# final.net
KiCad netlist of a schematic drawn in Altium Designer
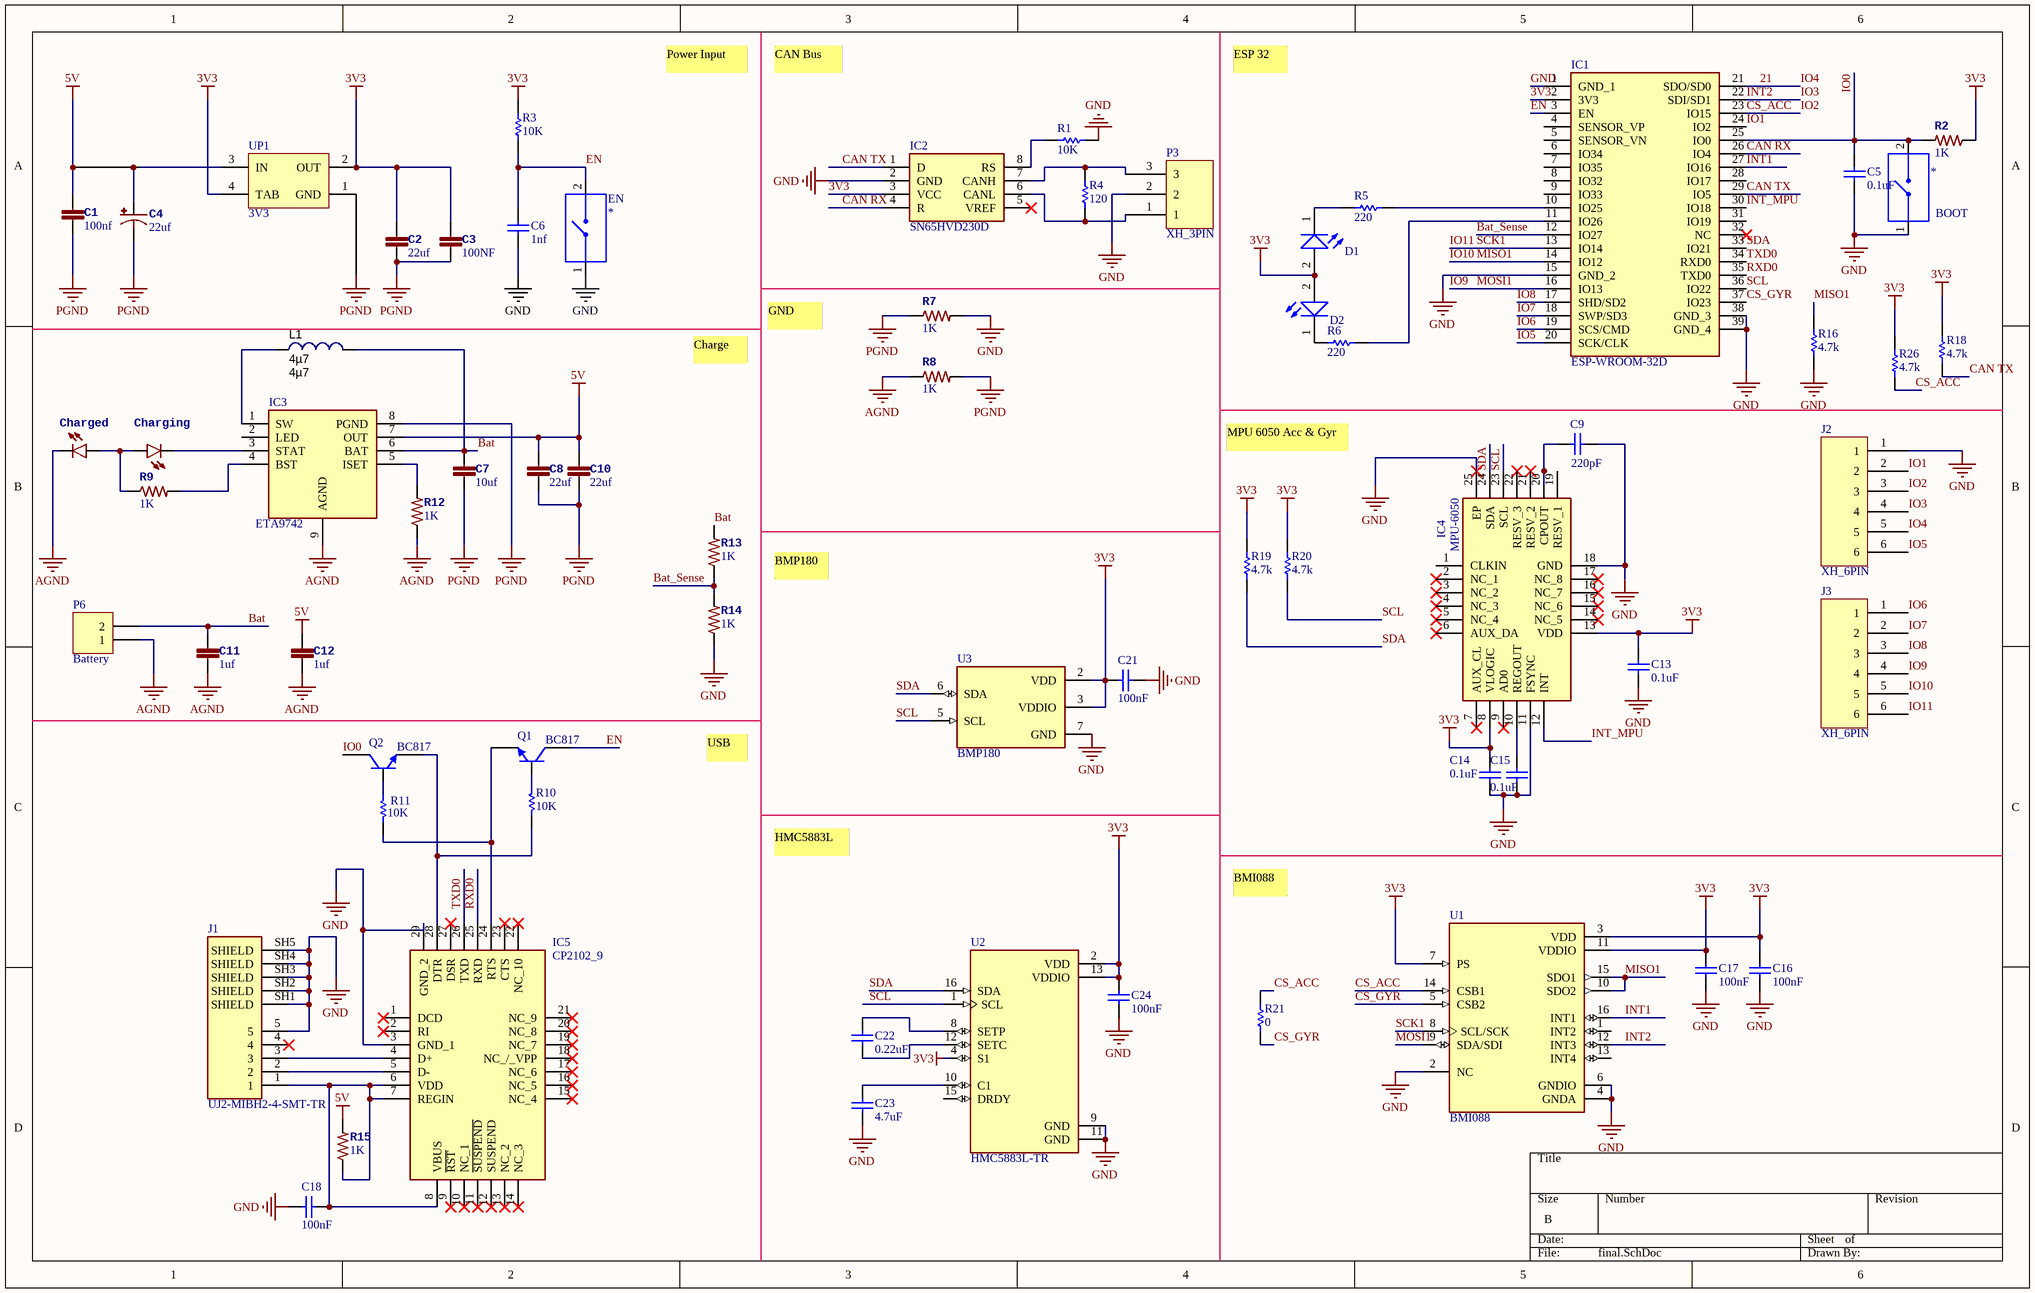
[diagram p0: final.SchDoc]

(export (version "E")
  (design (tool "Eeschema 10.0.6"))
  (components
    (comp (ref "BOOT")
      (value "1437566-4")
      (footprint "SW_1437566-4")
      (description "Switch Tactile OFF _ON_ SPST Rectangular Button Gull Wing 0.05A 12VDC 1.77N SMD T/R")
      (fields
        (field (name "MF") "TE Connectivity")
        (field (name "DIGI-KEY_PART_NUMBER") "450-1758-1-ND")
        (field (name "COMMENT_1") "*")
      )
      (libsource (lib "1437566-4") (part "1437566-4"))
    )
    (comp (ref "C1")
      (value "100nf")
      (footprint "_0805")
      (fields (field (name "Comment") "Cap"))
      (libsource (lib "Passives_Integrated_Library") (part "Cap_1"))
    )
    (comp (ref "C2")
      (value "22uf")
      (footprint "_0805")
      (fields (field (name "Comment") "Cap"))
      (libsource (lib "Passives_Integrated_Library") (part "Cap_1"))
    )
    (comp (ref "C3")
      (value "100NF")
      (footprint "_0805")
      (fields (field (name "Comment") "Cap"))
      (libsource (lib "Passives_Integrated_Library") (part "Cap_1"))
    )
    (comp (ref "C4")
      (value "22uf")
      (footprint "_EIA3216")
      (fields (field (name "Comment") "Cap-Pol"))
      (libsource (lib "Passives_Integrated_Library") (part "Cap-Pol"))
    )
    (comp (ref "C5")
      (value "0.1uF")
      (footprint "C0603")
      (description "CAP 0805")
      (fields (field (name "DESIGNER") "Abbas Basereh"))
      (libsource (lib "Altium") (part "CAP SMD 0805"))
    )
    (comp (ref "C6")
      (value "1nf")
      (footprint "C0603")
      (description "CAP 0805")
      (fields (field (name "DESIGNER") "Abbas Basereh"))
      (libsource (lib "Altium") (part "CAP SMD 0805"))
    )
    (comp (ref "C7")
      (value "10uf")
      (footprint "_0805")
      (fields (field (name "Comment") "Cap"))
      (libsource (lib "Passives_Integrated_Library") (part "Cap_1"))
    )
    (comp (ref "C8")
      (value "22uf")
      (footprint "_0805")
      (fields (field (name "Comment") "Cap"))
      (libsource (lib "Passives_Integrated_Library") (part "Cap_1"))
    )
    (comp (ref "C9")
      (value "220pF")
      (footprint "C0603")
      (description "CAP 0805")
      (fields (field (name "DESIGNER") "Abbas Basereh"))
      (libsource (lib "Altium") (part "CAP SMD 0805"))
    )
    (comp (ref "C10")
      (value "22uf")
      (footprint "_0805")
      (fields (field (name "Comment") "Cap"))
      (libsource (lib "Passives_Integrated_Library") (part "Cap_1"))
    )
    (comp (ref "C11")
      (value "1uf")
      (footprint "_0805")
      (fields (field (name "Comment") "Cap"))
      (libsource (lib "Passives_Integrated_Library") (part "Cap_1"))
    )
    (comp (ref "C12")
      (value "1uf")
      (footprint "_0805")
      (fields (field (name "Comment") "Cap"))
      (libsource (lib "Passives_Integrated_Library") (part "Cap_1"))
    )
    (comp (ref "C13")
      (value "0.1uF")
      (footprint "C0603")
      (description "CAP 0805")
      (fields (field (name "DESIGNER") "Abbas Basereh"))
      (libsource (lib "Altium") (part "CAP SMD 0805"))
    )
    (comp (ref "C14")
      (value "0.1uF")
      (footprint "C0603")
      (description "CAP 0805")
      (fields (field (name "DESIGNER") "Abbas Basereh"))
      (libsource (lib "Altium") (part "CAP SMD 0805"))
    )
    (comp (ref "C15")
      (value "0.1uF")
      (footprint "C0603")
      (description "CAP 0805")
      (fields (field (name "DESIGNER") "Abbas Basereh"))
      (libsource (lib "Altium") (part "CAP SMD 0805"))
    )
    (comp (ref "C16")
      (value "100nF")
      (footprint "C0603")
      (description "CAP 0805")
      (fields (field (name "DESIGNER") "Abbas Basereh"))
      (libsource (lib "Altium") (part "CAP SMD 0805"))
    )
    (comp (ref "C17")
      (value "100nF")
      (footprint "C0603")
      (description "CAP 0805")
      (fields (field (name "DESIGNER") "Abbas Basereh"))
      (libsource (lib "Altium") (part "CAP SMD 0805"))
    )
    (comp (ref "C18")
      (value "100nF")
      (footprint "C0603")
      (description "CAP 0805")
      (fields (field (name "DESIGNER") "Abbas Basereh"))
      (libsource (lib "Altium") (part "CAP SMD 0805"))
    )
    (comp (ref "C21")
      (value "100nF")
      (footprint "C0603")
      (description "CAP 0805")
      (fields (field (name "DESIGNER") "Abbas Basereh"))
      (libsource (lib "Altium") (part "CAP SMD 0805"))
    )
    (comp (ref "C22")
      (value "0.22uF")
      (footprint "C0603")
      (description "CAP 0805")
      (fields (field (name "DESIGNER") "Abbas Basereh"))
      (libsource (lib "Altium") (part "CAP SMD 0805"))
    )
    (comp (ref "C23")
      (value "4.7uF")
      (footprint "C0603")
      (description "CAP 0805")
      (fields (field (name "DESIGNER") "Abbas Basereh"))
      (libsource (lib "Altium") (part "CAP SMD 0805"))
    )
    (comp (ref "C24")
      (value "100nF")
      (footprint "C0603")
      (description "CAP 0805")
      (fields (field (name "DESIGNER") "Abbas Basereh"))
      (libsource (lib "Altium") (part "CAP SMD 0805"))
    )
    (comp (ref "Charged")
      (value "LED")
      (footprint "_LED-0805")
      (libsource (lib "Diodes_Integrated_Library") (part "LED"))
    )
    (comp (ref "Charging")
      (value "LED")
      (footprint "_LED-0805")
      (libsource (lib "Diodes_Integrated_Library") (part "LED"))
    )
    (comp (ref "D1")
      (value "LED SMD PACKAGE")
      (footprint "LED_SMD_0805")
      (description "SMD Mono-color Chip LED Waterclear")
      (fields (field (name "PART NUMBER") "150080BS75000") (field (name "PUBLISHER") "Ali Hafizi"))
      (libsource (lib "Altium") (part "LED SMD PACKAGE"))
    )
    (comp (ref "D2")
      (value "LED SMD PACKAGE")
      (footprint "LED_SMD_0805")
      (description "SMD Mono-color Chip LED Waterclear")
      (fields (field (name "PART NUMBER") "150080BS75000") (field (name "PUBLISHER") "Ali Hafizi"))
      (libsource (lib "Altium") (part "LED SMD PACKAGE"))
    )
    (comp (ref "EN")
      (value "1437566-4")
      (footprint "SW_1437566-4")
      (description "Switch Tactile OFF _ON_ SPST Rectangular Button Gull Wing 0.05A 12VDC 1.77N SMD T/R")
      (fields
        (field (name "MF") "TE Connectivity")
        (field (name "DIGI-KEY_PART_NUMBER") "450-1758-1-ND")
        (field (name "COMMENT_1") "*")
      )
      (libsource (lib "1437566-4") (part "1437566-4"))
    )
    (comp (ref "IC1")
      (value "ESP-WROOM-32D")
      (footprint "SamacSys:ESPWROOM32D")
      (description "Integrated Circuit")
      (fields (field (name "MOUSER PART NUMBER") "356-ESP-WROOM-32D"))
      (libsource (lib "SamacSys") (part "ESP-WROOM-32D"))
    )
    (comp (ref "IC2")
      (value "SN65HVD230D")
      (footprint "SamacSys:SOIC127P600X175-8N")
      (description "Integrated Circuit")
      (fields (field (name "MOUSER PART NUMBER") "595-SN65HVD230D"))
      (libsource (lib "*") (part "SN65HVD230D"))
    )
    (comp (ref "IC3")
      (value "ETA9742")
      (footprint "SamacSys:SOIC127P600X175-9N")
      (description "Integrated Circuit")
      (libsource (lib "*") (part "ETA9742"))
    )
    (comp (ref "IC4")
      (value "MPU-6050")
      (footprint "SamacSys:QFN50P400X400X95-25N")
      (description "Integrated Circuit")
      (fields (field (name "MOUSER PART NUMBER") "410-MPU-6050"))
      (libsource (lib "*") (part "MPU-6050"))
    )
    (comp (ref "IC5")
      (value "CP2102_9")
      (footprint "SamacSys:QFN50P500X500X105-29N-D")
      (description "Integrated Circuit")
      (fields (field (name "MANUFACTURER_PART_NUMBER") "CP2102/9"))
      (libsource (lib "*") (part "CP2102_9"))
    )
    (comp (ref "J1")
      (value "UJ2-MIBH2-4-SMT-TR")
      (footprint "CUI_UJ2-MIBH2-4-SMT-TR")
      (description "Micro B, USB 2.0, 1.8 A, Right Angle, Surface Mount _SMT_, USB Receptacle")
      (fields (field (name "MF") "CUI Devices"))
      (libsource (lib "UJ2-MIBH2-4-SMT-TR") (part "UJ2-MIBH2-4-SMT-TR"))
    )
    (comp (ref "J2")
      (value "XH_6PIN")
      (footprint "XH_6PIN")
      (libsource (lib "Others_Integrated_Library") (part "XH_6PIN"))
    )
    (comp (ref "J3")
      (value "XH_6PIN")
      (footprint "XH_6PIN")
      (libsource (lib "Others_Integrated_Library") (part "XH_6PIN"))
    )
    (comp (ref "L1")
      (value "4µ7")
      (footprint "Inductor SMD 3x3.2mm")
      (description "Inductor 4.7µH SMD 3x3.2mm")
      (fields (field (name "TOLERANCE") "±20%") (field (name "ALTIUM_VALUE") "4µ7"))
      (libsource (lib "Altium") (part "Inductor 4.7µH SMD 3x3.2mm"))
    )
    (comp (ref "P3")
      (value "XH_3PIN")
      (footprint "XH_3PIN")
      (libsource (lib "Others_Integrated_Library") (part "XH_3PIN"))
    )
    (comp (ref "P6")
      (value "Battery")
      (footprint "HDR1X2")
      (description "Header, 2-Pin")
      (fields (field (name "PUBLISHER") "Altium Limited"))
      (libsource (lib "Altium") (part "Header 2"))
    )
    (comp (ref "Q1")
      (value "BC817")
      (footprint "SOT23_N")
      (description "45 V, 500 mA NPN general-purpose transistors")
      (fields (field (name "PUBLISHER") "Abbas Basereh"))
      (libsource (lib "Altium") (part "BC817"))
    )
    (comp (ref "Q2")
      (value "BC817")
      (footprint "SOT23_N")
      (description "45 V, 500 mA NPN general-purpose transistors")
      (fields (field (name "PUBLISHER") "Abbas Basereh"))
      (libsource (lib "Altium") (part "BC817"))
    )
    (comp (ref "R1")
      (value "10K")
      (footprint "SMD-0603-RES")
      (description "Resistor SMD 0603")
      (libsource (lib "Resistor") (part "Resistor SMD 0603"))
    )
    (comp (ref "R2")
      (value "1K")
      (footprint "_0805")
      (fields (field (name "Comment") "Resistor"))
      (libsource (lib "Passives_Integrated_Library") (part "Resistor"))
    )
    (comp (ref "R3")
      (value "10K")
      (footprint "RES0805")
      (description "TOTAL SMD RESISTOR PACK")
      (fields (field (name "DESIGNER") "Abbas Basereh"))
      (libsource (lib "Altium") (part "RES SMD PACKAGE"))
    )
    (comp (ref "R4")
      (value "120")
      (footprint "SMD-0603-RES")
      (description "Resistor SMD 0603")
      (libsource (lib "Resistor") (part "Resistor SMD 0603"))
    )
    (comp (ref "R5")
      (value "220")
      (footprint "SMD-0603-RES")
      (description "Resistor SMD 0603")
      (libsource (lib "Resistor") (part "Resistor SMD 0603"))
    )
    (comp (ref "R6")
      (value "220")
      (footprint "SMD-0603-RES")
      (description "Resistor SMD 0603")
      (libsource (lib "Resistor") (part "Resistor SMD 0603"))
    )
    (comp (ref "R7")
      (value "1K")
      (footprint "_0805")
      (fields (field (name "Comment") "Resistor"))
      (libsource (lib "Passives_Integrated_Library") (part "Resistor"))
    )
    (comp (ref "R8")
      (value "1K")
      (footprint "_0805")
      (fields (field (name "Comment") "Resistor"))
      (libsource (lib "Passives_Integrated_Library") (part "Resistor"))
    )
    (comp (ref "R9")
      (value "1K")
      (footprint "_0805")
      (fields (field (name "Comment") "Resistor"))
      (libsource (lib "Passives_Integrated_Library") (part "Resistor"))
    )
    (comp (ref "R10")
      (value "10K")
      (footprint "SMD-0603-RES")
      (description "Resistor SMD 0603")
      (libsource (lib "Resistor") (part "Resistor SMD 0603"))
    )
    (comp (ref "R11")
      (value "10K")
      (footprint "SMD-0603-RES")
      (description "Resistor SMD 0603")
      (libsource (lib "Resistor") (part "Resistor SMD 0603"))
    )
    (comp (ref "R12")
      (value "1K")
      (footprint "_0805")
      (fields (field (name "Comment") "Resistor"))
      (libsource (lib "Passives_Integrated_Library") (part "Resistor"))
    )
    (comp (ref "R13")
      (value "1K")
      (footprint "_0805")
      (fields (field (name "Comment") "Resistor"))
      (libsource (lib "Passives_Integrated_Library") (part "Resistor"))
    )
    (comp (ref "R14")
      (value "1K")
      (footprint "_0805")
      (fields (field (name "Comment") "Resistor"))
      (libsource (lib "Passives_Integrated_Library") (part "Resistor"))
    )
    (comp (ref "R15")
      (value "1K")
      (footprint "_0805")
      (fields (field (name "Comment") "Resistor"))
      (libsource (lib "Passives_Integrated_Library") (part "Resistor"))
    )
    (comp (ref "R16")
      (value "4.7k")
      (footprint "SMD-0603-RES")
      (description "Resistor SMD 0603")
      (libsource (lib "Resistor") (part "Resistor SMD 0603"))
    )
    (comp (ref "R18")
      (value "4.7k")
      (footprint "SMD-0603-RES")
      (description "Resistor SMD 0603")
      (libsource (lib "Resistor") (part "Resistor SMD 0603"))
    )
    (comp (ref "R19")
      (value "4.7k")
      (footprint "SMD-0603-RES")
      (description "Resistor SMD 0603")
      (libsource (lib "Resistor") (part "Resistor SMD 0603"))
    )
    (comp (ref "R20")
      (value "4.7k")
      (footprint "SMD-0603-RES")
      (description "Resistor SMD 0603")
      (libsource (lib "Resistor") (part "Resistor SMD 0603"))
    )
    (comp (ref "R21")
      (value "0")
      (footprint "SMD-0603-RES")
      (description "Resistor SMD 0603")
      (libsource (lib "Resistor") (part "Resistor SMD 0603"))
    )
    (comp (ref "R26")
      (value "4.7k")
      (footprint "SMD-0603-RES")
      (description "Resistor SMD 0603")
      (libsource (lib "Resistor") (part "Resistor SMD 0603"))
    )
    (comp (ref "U1")
      (value "BMI088")
      (footprint "PQFN50P450X300X100-16N")
      (description "Accelerometer, Gyroscope, 6 Axis Sensor IÂ²C, SPI Output")
      (fields (field (name "MF") "Bosch Sensortec"))
      (libsource (lib "BMI088") (part "BMI088"))
    )
    (comp (ref "U2")
      (value "HMC5883L-TR")
      (footprint "XDCR_HMC5883L-TR")
      (description "Magnetoresistive Sensor X, Y, Z Axis 16-LCC")
      (fields (field (name "MF") "Honeywell") (field (name "MP") "HMC5883LTR"))
      (libsource (lib "HMC5883L-TR") (part "HMC5883L-TR"))
    )
    (comp (ref "U3")
      (value "BMP180")
      (footprint "BMP180")
      (description "Pressure Sensor 4.35PSI ~ 15.95PSI _30kPa ~ 110kPa_ Absolute 16 ~ 19 b 7-VLGA")
      (fields (field (name "MF") "Bosch Sensortec") (field (name "DIGI-KEY_PART_NUMBER") "828-1027-1-ND"))
      (libsource (lib "BMP180") (part "BMP180"))
    )
    (comp (ref "UP1")
      (value "3V3")
      (footprint "SOT223_N")
      (description "x.x Volt, 800mA Low-Dropout Linear Regulator, 4-pin SOT-223")
      (fields (field (name "DESIGNER") "Ali Hafizi"))
      (libsource (lib "Altium") (part "AMS1117-x.x"))
    )
  )
  (nets
    (net (code "1") (name "/21") (class "Default")
      (node (ref "IC1") (pin "21") (pinfunction "SDO/SD0_21") (pintype "passive"))
      (node (ref "J2") (pin "5") (pinfunction "5_5") (pintype "passive"))
    )
    (net (code "2") (name "/Bat") (class "Default")
      (node (ref "C11") (pin "1") (pinfunction "1_1") (pintype "passive"))
      (node (ref "C7") (pin "1") (pinfunction "1_1") (pintype "passive"))
      (node (ref "IC3") (pin "6") (pinfunction "BAT_6") (pintype "passive"))
      (node (ref "L1") (pin "2") (pinfunction "2_2") (pintype "passive"))
      (node (ref "P6") (pin "2") (pinfunction "2_2") (pintype "passive"))
      (node (ref "R13") (pin "2") (pinfunction "2_2") (pintype "passive"))
    )
    (net (code "3") (name "/Bat_Sense") (class "Default")
      (node (ref "IC1") (pin "12") (pinfunction "IO27_12") (pintype "passive"))
      (node (ref "R13") (pin "1") (pinfunction "1_1") (pintype "passive"))
      (node (ref "R14") (pin "2") (pinfunction "2_2") (pintype "passive"))
    )
    (net (code "4") (name "/CAN RX") (class "Default")
      (node (ref "IC1") (pin "26") (pinfunction "IO4_26") (pintype "passive"))
      (node (ref "IC2") (pin "4") (pinfunction "R_4") (pintype "passive"))
    )
    (net (code "5") (name "/CAN TX") (class "Default")
      (node (ref "IC1") (pin "29") (pinfunction "IO5_29") (pintype "passive"))
      (node (ref "IC2") (pin "1") (pinfunction "D_1") (pintype "passive"))
      (node (ref "R18") (pin "1") (pinfunction "1_1") (pintype "passive"))
    )
    (net (code "6") (name "/CS_ACC") (class "Default")
      (node (ref "IC1") (pin "23") (pinfunction "IO15_23") (pintype "passive"))
      (node (ref "J2") (pin "3") (pinfunction "3_3") (pintype "passive"))
      (node (ref "R21") (pin "2") (pinfunction "2_2") (pintype "passive"))
      (node (ref "R26") (pin "1") (pinfunction "1_1") (pintype "passive"))
      (node (ref "U1") (pin "14") (pinfunction "CSB1_14") (pintype "input"))
    )
    (net (code "7") (name "/CS_GYR") (class "Default")
      (node (ref "IC1") (pin "37") (pinfunction "IO23_37") (pintype "passive"))
      (node (ref "R21") (pin "1") (pinfunction "1_1") (pintype "passive"))
      (node (ref "U1") (pin "5") (pinfunction "CSB2_5") (pintype "input"))
    )
    (net (code "8") (name "/EN") (class "Default")
      (node (ref "C6") (pin "2") (pinfunction "2_2") (pintype "passive"))
      (node (ref "EN") (pin "2") (pinfunction "2_2") (pintype "passive"))
      (node (ref "IC1") (pin "3") (pinfunction "EN_3") (pintype "passive"))
      (node (ref "Q1") (pin "3") (pinfunction "C_3") (pintype "passive"))
      (node (ref "R3") (pin "1") (pinfunction "1_1") (pintype "passive"))
    )
    (net (code "9") (name "/INT1") (class "Default")
      (node (ref "IC1") (pin "27") (pinfunction "IO16_27") (pintype "passive"))
      (node (ref "U1") (pin "16") (pinfunction "INT1_16") (pintype "bidirectional"))
    )
    (net (code "10") (name "/INT2") (class "Default")
      (node (ref "IC1") (pin "22") (pinfunction "SDI/SD1_22") (pintype "passive"))
      (node (ref "J2") (pin "4") (pinfunction "4_4") (pintype "passive"))
      (node (ref "U1") (pin "12") (pinfunction "INT3_12") (pintype "bidirectional"))
    )
    (net (code "11") (name "/INT_MPU") (class "Default")
      (node (ref "IC1") (pin "30") (pinfunction "IO18_30") (pintype "passive"))
      (node (ref "IC4") (pin "12") (pinfunction "INT_12") (pintype "passive"))
    )
    (net (code "12") (name "/IO0") (class "Default")
      (node (ref "BOOT") (pin "2") (pinfunction "2_2") (pintype "passive"))
      (node (ref "C5") (pin "2") (pinfunction "2_2") (pintype "passive"))
      (node (ref "IC1") (pin "25") (pinfunction "IO0_25") (pintype "passive"))
      (node (ref "Q2") (pin "3") (pinfunction "C_3") (pintype "passive"))
      (node (ref "R2") (pin "2") (pinfunction "2_2") (pintype "passive"))
    )
    (net (code "13") (name "/IO1") (class "Default")
      (node (ref "IC1") (pin "24") (pinfunction "IO2_24") (pintype "passive"))
      (node (ref "J2") (pin "2") (pinfunction "2_2") (pintype "passive"))
    )
    (net (code "14") (name "/IO5") (class "Default")
      (node (ref "IC1") (pin "20") (pinfunction "SCK/CLK_20") (pintype "passive"))
      (node (ref "J2") (pin "6") (pinfunction "6_6") (pintype "passive"))
    )
    (net (code "15") (name "/IO6") (class "Default")
      (node (ref "IC1") (pin "19") (pinfunction "SCS/CMD_19") (pintype "passive"))
      (node (ref "J3") (pin "1") (pinfunction "1_1") (pintype "passive"))
    )
    (net (code "16") (name "/IO7") (class "Default")
      (node (ref "IC1") (pin "18") (pinfunction "SWP/SD3_18") (pintype "passive"))
      (node (ref "J3") (pin "2") (pinfunction "2_2") (pintype "passive"))
    )
    (net (code "17") (name "/IO8") (class "Default")
      (node (ref "IC1") (pin "17") (pinfunction "SHD/SD2_17") (pintype "passive"))
      (node (ref "J3") (pin "3") (pinfunction "3_3") (pintype "passive"))
    )
    (net (code "18") (name "/IO9") (class "Default")
      (node (ref "IC1") (pin "16") (pinfunction "IO13_16") (pintype "passive"))
      (node (ref "J3") (pin "4") (pinfunction "4_4") (pintype "passive"))
      (node (ref "U1") (pin "9") (pinfunction "SDA/SDI_9") (pintype "bidirectional"))
    )
    (net (code "19") (name "/IO10") (class "Default")
      (node (ref "IC1") (pin "14") (pinfunction "IO12_14") (pintype "passive"))
      (node (ref "J3") (pin "5") (pinfunction "5_5") (pintype "passive"))
      (node (ref "R16") (pin "2") (pinfunction "2_2") (pintype "passive"))
      (node (ref "U1") (pin "10") (pinfunction "SDO2_10") (pintype "output"))
      (node (ref "U1") (pin "15") (pinfunction "SDO1_15") (pintype "output"))
    )
    (net (code "20") (name "/IO11") (class "Default")
      (node (ref "IC1") (pin "13") (pinfunction "IO14_13") (pintype "passive"))
      (node (ref "J3") (pin "6") (pinfunction "6_6") (pintype "passive"))
      (node (ref "U1") (pin "8") (pinfunction "SCL/SCK_8") (pintype "input"))
    )
    (net (code "21") (name "/RXD0") (class "Default")
      (node (ref "IC1") (pin "35") (pinfunction "TXD0_35") (pintype "passive"))
      (node (ref "IC5") (pin "25") (pinfunction "RXD_25") (pintype "passive"))
    )
    (net (code "22") (name "/SCL") (class "Default")
      (node (ref "IC1") (pin "36") (pinfunction "IO22_36") (pintype "passive"))
      (node (ref "IC4") (pin "23") (pinfunction "SCL_23") (pintype "passive"))
      (node (ref "R20") (pin "1") (pinfunction "1_1") (pintype "passive"))
      (node (ref "U2") (pin "1") (pinfunction "SCL_1") (pintype "input"))
      (node (ref "U3") (pin "5") (pinfunction "SCL_5") (pintype "input"))
    )
    (net (code "23") (name "/SDA") (class "Default")
      (node (ref "IC1") (pin "33") (pinfunction "IO21_33") (pintype "passive"))
      (node (ref "IC4") (pin "24") (pinfunction "SDA_24") (pintype "passive"))
      (node (ref "R19") (pin "1") (pinfunction "1_1") (pintype "passive"))
      (node (ref "U2") (pin "16") (pinfunction "SDA_16") (pintype "input"))
      (node (ref "U3") (pin "6") (pinfunction "SDA_6") (pintype "bidirectional"))
    )
    (net (code "24") (name "/TXD0") (class "Default")
      (node (ref "IC1") (pin "34") (pinfunction "RXD0_34") (pintype "passive"))
      (node (ref "IC5") (pin "26") (pinfunction "TXD_26") (pintype "passive"))
    )
    (net (code "25") (name "3V3") (class "Default")
      (node (ref "C13") (pin "2") (pinfunction "2_2") (pintype "passive"))
      (node (ref "C14") (pin "1") (pinfunction "1_1") (pintype "passive"))
      (node (ref "C16") (pin "2") (pinfunction "2_2") (pintype "passive"))
      (node (ref "C17") (pin "2") (pinfunction "2_2") (pintype "passive"))
      (node (ref "C2") (pin "1") (pinfunction "1_1") (pintype "passive"))
      (node (ref "C21") (pin "2") (pinfunction "2_2") (pintype "passive"))
      (node (ref "C24") (pin "1") (pinfunction "1_1") (pintype "passive"))
      (node (ref "C3") (pin "1") (pinfunction "1_1") (pintype "passive"))
      (node (ref "D1") (pin "2") (pinfunction "A_2") (pintype "passive"))
      (node (ref "D2") (pin "2") (pinfunction "A_2") (pintype "passive"))
      (node (ref "IC1") (pin "2") (pinfunction "3V3_2") (pintype "passive"))
      (node (ref "IC2") (pin "3") (pinfunction "VCC_3") (pintype "passive"))
      (node (ref "IC4") (pin "13") (pinfunction "VDD_13") (pintype "passive"))
      (node (ref "IC4") (pin "8") (pinfunction "VLOGIC_8") (pintype "passive"))
      (node (ref "R18") (pin "2") (pinfunction "2_2") (pintype "passive"))
      (node (ref "R19") (pin "2") (pinfunction "2_2") (pintype "passive"))
      (node (ref "R2") (pin "1") (pinfunction "1_1") (pintype "passive"))
      (node (ref "R20") (pin "2") (pinfunction "2_2") (pintype "passive"))
      (node (ref "R26") (pin "2") (pinfunction "2_2") (pintype "passive"))
      (node (ref "R3") (pin "2") (pinfunction "2_2") (pintype "passive"))
      (node (ref "U1") (pin "11") (pinfunction "VDDIO_11") (pintype "power_in"))
      (node (ref "U1") (pin "3") (pinfunction "VDD_3") (pintype "power_in"))
      (node (ref "U1") (pin "7") (pinfunction "PS_7") (pintype "input"))
      (node (ref "U2") (pin "13") (pinfunction "VDDIO_13") (pintype "power_in"))
      (node (ref "U2") (pin "2") (pinfunction "VDD_2") (pintype "power_in"))
      (node (ref "U2") (pin "4") (pinfunction "S1_4") (pintype "bidirectional"))
      (node (ref "U3") (pin "2") (pinfunction "VDD_2") (pintype "power_in"))
      (node (ref "U3") (pin "3") (pinfunction "VDDIO_3") (pintype "power_in"))
      (node (ref "UP1") (pin "2") (pinfunction "OUT_2") (pintype "power_in"))
      (node (ref "UP1") (pin "4") (pinfunction "TAB_4") (pintype "power_in"))
    )
    (net (code "26") (name "5V") (class "Default")
      (node (ref "C1") (pin "1") (pinfunction "1_1") (pintype "passive"))
      (node (ref "C10") (pin "1") (pinfunction "1_1") (pintype "passive"))
      (node (ref "C12") (pin "1") (pinfunction "1_1") (pintype "passive"))
      (node (ref "C4") (pin "+") (pinfunction "+_+") (pintype "passive"))
      (node (ref "C8") (pin "1") (pinfunction "1_1") (pintype "passive"))
      (node (ref "IC3") (pin "7") (pinfunction "OUT_7") (pintype "passive"))
      (node (ref "R15") (pin "2") (pinfunction "2_2") (pintype "passive"))
      (node (ref "UP1") (pin "3") (pinfunction "IN_3") (pintype "power_in"))
    )
    (net (code "27") (name "AGND") (class "Default")
      (node (ref "C11") (pin "2") (pinfunction "2_2") (pintype "passive"))
      (node (ref "C12") (pin "2") (pinfunction "2_2") (pintype "passive"))
      (node (ref "Charged") (pin "K") (pinfunction "K_K") (pintype "passive"))
      (node (ref "IC3") (pin "9") (pinfunction "AGND_9") (pintype "passive"))
      (node (ref "P6") (pin "1") (pinfunction "1_1") (pintype "passive"))
      (node (ref "R12") (pin "1") (pinfunction "1_1") (pintype "passive"))
      (node (ref "R8") (pin "1") (pinfunction "1_1") (pintype "passive"))
    )
    (net (code "28") (name "GND") (class "Default")
      (node (ref "BOOT") (pin "1") (pinfunction "1_1") (pintype "passive"))
      (node (ref "C13") (pin "1") (pinfunction "1_1") (pintype "passive"))
      (node (ref "C14") (pin "2") (pinfunction "2_2") (pintype "passive"))
      (node (ref "C15") (pin "1") (pinfunction "1_1") (pintype "passive"))
      (node (ref "C16") (pin "1") (pinfunction "1_1") (pintype "passive"))
      (node (ref "C17") (pin "1") (pinfunction "1_1") (pintype "passive"))
      (node (ref "C18") (pin "2") (pinfunction "2_2") (pintype "passive"))
      (node (ref "C21") (pin "1") (pinfunction "1_1") (pintype "passive"))
      (node (ref "C23") (pin "1") (pinfunction "1_1") (pintype "passive"))
      (node (ref "C24") (pin "2") (pinfunction "2_2") (pintype "passive"))
      (node (ref "C5") (pin "1") (pinfunction "1_1") (pintype "passive"))
      (node (ref "C6") (pin "1") (pinfunction "1_1") (pintype "passive"))
      (node (ref "C9") (pin "1") (pinfunction "1_1") (pintype "passive"))
      (node (ref "EN") (pin "1") (pinfunction "1_1") (pintype "passive"))
      (node (ref "IC1") (pin "1") (pinfunction "GND_1_1") (pintype "passive"))
      (node (ref "IC1") (pin "15") (pinfunction "GND_2_15") (pintype "passive"))
      (node (ref "IC1") (pin "38") (pinfunction "GND_3_38") (pintype "passive"))
      (node (ref "IC1") (pin "39") (pinfunction "GND_4_39") (pintype "passive"))
      (node (ref "IC2") (pin "2") (pinfunction "GND_2") (pintype "passive"))
      (node (ref "IC4") (pin "11") (pinfunction "FSYNC_11") (pintype "passive"))
      (node (ref "IC4") (pin "18") (pinfunction "GND_18") (pintype "passive"))
      (node (ref "IC4") (pin "25") (pinfunction "EP_25") (pintype "passive"))
      (node (ref "IC5") (pin "29") (pinfunction "GND_2_29") (pintype "passive"))
      (node (ref "IC5") (pin "3") (pinfunction "GND_1_3") (pintype "passive"))
      (node (ref "J1") (pin "5") (pinfunction "5_5") (pintype "passive"))
      (node (ref "J1") (pin "SH1") (pinfunction "SHIELD_SH1") (pintype "passive"))
      (node (ref "J1") (pin "SH2") (pinfunction "SHIELD_SH2") (pintype "passive"))
      (node (ref "J1") (pin "SH3") (pinfunction "SHIELD_SH3") (pintype "passive"))
      (node (ref "J1") (pin "SH4") (pinfunction "SHIELD_SH4") (pintype "passive"))
      (node (ref "J1") (pin "SH5") (pinfunction "SHIELD_SH5") (pintype "passive"))
      (node (ref "J2") (pin "1") (pinfunction "1_1") (pintype "passive"))
      (node (ref "P3") (pin "2") (pinfunction "2_2") (pintype "passive"))
      (node (ref "R1") (pin "1") (pinfunction "1_1") (pintype "passive"))
      (node (ref "R14") (pin "1") (pinfunction "1_1") (pintype "passive"))
      (node (ref "R16") (pin "1") (pinfunction "1_1") (pintype "passive"))
      (node (ref "R7") (pin "2") (pinfunction "2_2") (pintype "passive"))
      (node (ref "U1") (pin "2") (pinfunction "NC_2") (pintype "passive"))
      (node (ref "U1") (pin "4") (pinfunction "GNDA_4") (pintype "power_in"))
      (node (ref "U1") (pin "6") (pinfunction "GNDIO_6") (pintype "power_in"))
      (node (ref "U2") (pin "11") (pinfunction "GND_11") (pintype "power_in"))
      (node (ref "U2") (pin "9") (pinfunction "GND_9") (pintype "power_in"))
      (node (ref "U3") (pin "7") (pinfunction "GND_7") (pintype "power_in"))
    )
    (net (code "29") (name "Net-(Charged-PadA)") (class "Default")
      (node (ref "Charged") (pin "A") (pinfunction "A_A") (pintype "passive"))
      (node (ref "Charging") (pin "A") (pinfunction "A_A") (pintype "passive"))
      (node (ref "R9") (pin "1") (pinfunction "1_1") (pintype "passive"))
    )
    (net (code "30") (name "Net-(D1-K)") (class "Default")
      (node (ref "D1") (pin "1") (pinfunction "K_1") (pintype "passive"))
      (node (ref "R5") (pin "2") (pinfunction "2_2") (pintype "passive"))
    )
    (net (code "31") (name "Net-(D2-K)") (class "Default")
      (node (ref "D2") (pin "1") (pinfunction "K_1") (pintype "passive"))
      (node (ref "R6") (pin "2") (pinfunction "2_2") (pintype "passive"))
    )
    (net (code "32") (name "Net-(IC1-IO25)") (class "Default")
      (node (ref "IC1") (pin "10") (pinfunction "IO25_10") (pintype "passive"))
      (node (ref "R5") (pin "1") (pinfunction "1_1") (pintype "passive"))
    )
    (net (code "33") (name "Net-(IC1-IO26)") (class "Default")
      (node (ref "IC1") (pin "11") (pinfunction "IO26_11") (pintype "passive"))
      (node (ref "R6") (pin "1") (pinfunction "1_1") (pintype "passive"))
    )
    (net (code "34") (name "Net-(IC2-CANH)") (class "Default")
      (node (ref "IC2") (pin "7") (pinfunction "CANH_7") (pintype "passive"))
      (node (ref "P3") (pin "3") (pinfunction "3_3") (pintype "passive"))
      (node (ref "R4") (pin "2") (pinfunction "2_2") (pintype "passive"))
    )
    (net (code "35") (name "Net-(IC2-CANL)") (class "Default")
      (node (ref "IC2") (pin "6") (pinfunction "CANL_6") (pintype "passive"))
      (node (ref "P3") (pin "1") (pinfunction "1_1") (pintype "passive"))
      (node (ref "R4") (pin "1") (pinfunction "1_1") (pintype "passive"))
    )
    (net (code "36") (name "Net-(IC2-RS)") (class "Default")
      (node (ref "IC2") (pin "8") (pinfunction "RS_8") (pintype "passive"))
      (node (ref "R1") (pin "2") (pinfunction "2_2") (pintype "passive"))
    )
    (net (code "37") (name "Net-(IC3-BST)") (class "Default")
      (node (ref "IC3") (pin "4") (pinfunction "BST_4") (pintype "passive"))
      (node (ref "R9") (pin "2") (pinfunction "2_2") (pintype "passive"))
    )
    (net (code "38") (name "Net-(IC3-ISET)") (class "Default")
      (node (ref "IC3") (pin "5") (pinfunction "ISET_5") (pintype "passive"))
      (node (ref "R12") (pin "2") (pinfunction "2_2") (pintype "passive"))
    )
    (net (code "39") (name "Net-(IC3-STAT)") (class "Default")
      (node (ref "Charging") (pin "K") (pinfunction "K_K") (pintype "passive"))
      (node (ref "IC3") (pin "3") (pinfunction "STAT_3") (pintype "passive"))
    )
    (net (code "40") (name "Net-(IC3-SW)") (class "Default")
      (node (ref "IC3") (pin "1") (pinfunction "SW_1") (pintype "passive"))
      (node (ref "L1") (pin "1") (pinfunction "1_1") (pintype "passive"))
    )
    (net (code "41") (name "Net-(IC4-CPOUT)") (class "Default")
      (node (ref "C9") (pin "2") (pinfunction "2_2") (pintype "passive"))
      (node (ref "IC4") (pin "20") (pinfunction "CPOUT_20") (pintype "passive"))
    )
    (net (code "42") (name "Net-(IC4-REGOUT)") (class "Default")
      (node (ref "C15") (pin "2") (pinfunction "2_2") (pintype "passive"))
      (node (ref "IC4") (pin "10") (pinfunction "REGOUT_10") (pintype "passive"))
    )
    (net (code "43") (name "Net-(IC5-D+)") (class "Default")
      (node (ref "IC5") (pin "4") (pinfunction "D+_4") (pintype "passive"))
      (node (ref "J1") (pin "3") (pinfunction "3_3") (pintype "passive"))
    )
    (net (code "44") (name "Net-(IC5-D-)") (class "Default")
      (node (ref "IC5") (pin "5") (pinfunction "D-_5") (pintype "passive"))
      (node (ref "J1") (pin "2") (pinfunction "2_2") (pintype "passive"))
    )
    (net (code "45") (name "Net-(IC5-DTR)") (class "Default")
      (node (ref "IC5") (pin "28") (pinfunction "DTR_28") (pintype "passive"))
      (node (ref "Q2") (pin "2") (pinfunction "E_2") (pintype "passive"))
      (node (ref "R10") (pin "1") (pinfunction "1_1") (pintype "passive"))
    )
    (net (code "46") (name "Net-(IC5-REGIN)") (class "Default")
      (node (ref "C18") (pin "1") (pinfunction "1_1") (pintype "passive"))
      (node (ref "IC5") (pin "6") (pinfunction "VDD_6") (pintype "passive"))
      (node (ref "IC5") (pin "7") (pinfunction "REGIN_7") (pintype "passive"))
      (node (ref "IC5") (pin "8") (pinfunction "VBUS_8") (pintype "passive"))
      (node (ref "J1") (pin "1") (pinfunction "1_1") (pintype "passive"))
      (node (ref "R15") (pin "1") (pinfunction "1_1") (pintype "passive"))
    )
    (net (code "47") (name "Net-(IC5-RTS)") (class "Default")
      (node (ref "IC5") (pin "24") (pinfunction "RTS_24") (pintype "passive"))
      (node (ref "Q1") (pin "2") (pinfunction "E_2") (pintype "passive"))
      (node (ref "R11") (pin "1") (pinfunction "1_1") (pintype "passive"))
    )
    (net (code "48") (name "Net-(Q1-B)") (class "Default")
      (node (ref "Q1") (pin "1") (pinfunction "B_1") (pintype "passive"))
      (node (ref "R10") (pin "2") (pinfunction "2_2") (pintype "passive"))
    )
    (net (code "49") (name "Net-(Q2-B)") (class "Default")
      (node (ref "Q2") (pin "1") (pinfunction "B_1") (pintype "passive"))
      (node (ref "R11") (pin "2") (pinfunction "2_2") (pintype "passive"))
    )
    (net (code "50") (name "Net-(U2-C1)") (class "Default")
      (node (ref "C23") (pin "2") (pinfunction "2_2") (pintype "passive"))
      (node (ref "U2") (pin "10") (pinfunction "C1_10") (pintype "bidirectional"))
    )
    (net (code "51") (name "Net-(U2-SETC)") (class "Default")
      (node (ref "C22") (pin "1") (pinfunction "1_1") (pintype "passive"))
      (node (ref "U2") (pin "12") (pinfunction "SETC_12") (pintype "bidirectional"))
    )
    (net (code "52") (name "Net-(U2-SETP)") (class "Default")
      (node (ref "C22") (pin "2") (pinfunction "2_2") (pintype "passive"))
      (node (ref "U2") (pin "8") (pinfunction "SETP_8") (pintype "bidirectional"))
    )
    (net (code "53") (name "PGND") (class "Default")
      (node (ref "C1") (pin "2") (pinfunction "2_2") (pintype "passive"))
      (node (ref "C10") (pin "2") (pinfunction "2_2") (pintype "passive"))
      (node (ref "C2") (pin "2") (pinfunction "2_2") (pintype "passive"))
      (node (ref "C3") (pin "2") (pinfunction "2_2") (pintype "passive"))
      (node (ref "C4") (pin "-") (pinfunction "-_-") (pintype "passive"))
      (node (ref "C7") (pin "2") (pinfunction "2_2") (pintype "passive"))
      (node (ref "C8") (pin "2") (pinfunction "2_2") (pintype "passive"))
      (node (ref "IC3") (pin "8") (pinfunction "PGND_8") (pintype "passive"))
      (node (ref "R7") (pin "1") (pinfunction "1_1") (pintype "passive"))
      (node (ref "R8") (pin "2") (pinfunction "2_2") (pintype "passive"))
      (node (ref "UP1") (pin "1") (pinfunction "GND_1") (pintype "power_in"))
    )
    (net (code "54") (name "unconnected-(IC1-IO17-Pad28)") (class "Default")
      (node (ref "IC1") (pin "28") (pinfunction "IO17_28") (pintype "passive"))
    )
    (net (code "55") (name "unconnected-(IC1-IO19-Pad31)") (class "Default")
      (node (ref "IC1") (pin "31") (pinfunction "IO19_31") (pintype "passive"))
    )
    (net (code "56") (name "unconnected-(IC1-IO32-Pad8)") (class "Default")
      (node (ref "IC1") (pin "8") (pinfunction "IO32_8") (pintype "passive"))
    )
    (net (code "57") (name "unconnected-(IC1-IO33-Pad9)") (class "Default")
      (node (ref "IC1") (pin "9") (pinfunction "IO33_9") (pintype "passive"))
    )
    (net (code "58") (name "unconnected-(IC1-IO34-Pad6)") (class "Default")
      (node (ref "IC1") (pin "6") (pinfunction "IO34_6") (pintype "passive"))
    )
    (net (code "59") (name "unconnected-(IC1-IO35-Pad7)") (class "Default")
      (node (ref "IC1") (pin "7") (pinfunction "IO35_7") (pintype "passive"))
    )
    (net (code "60") (name "unconnected-(IC1-NC-Pad32)") (class "Default")
      (node (ref "IC1") (pin "32") (pinfunction "NC_32") (pintype "passive+no_connect"))
    )
    (net (code "61") (name "unconnected-(IC1-SENSOR_VN-Pad5)") (class "Default")
      (node (ref "IC1") (pin "5") (pinfunction "SENSOR_VN_5") (pintype "passive"))
    )
    (net (code "62") (name "unconnected-(IC1-SENSOR_VP-Pad4)") (class "Default")
      (node (ref "IC1") (pin "4") (pinfunction "SENSOR_VP_4") (pintype "passive"))
    )
    (net (code "63") (name "unconnected-(IC2-VREF-Pad5)") (class "Default")
      (node (ref "IC2") (pin "5") (pinfunction "VREF_5") (pintype "passive+no_connect"))
    )
    (net (code "64") (name "unconnected-(IC3-LED-Pad2)") (class "Default")
      (node (ref "IC3") (pin "2") (pinfunction "LED_2") (pintype "passive"))
    )
    (net (code "65") (name "unconnected-(IC4-AD0-Pad9)") (class "Default")
      (node (ref "IC4") (pin "9") (pinfunction "AD0_9") (pintype "passive+no_connect"))
    )
    (net (code "66") (name "unconnected-(IC4-AUX_CL-Pad7)") (class "Default")
      (node (ref "IC4") (pin "7") (pinfunction "AUX_CL_7") (pintype "passive+no_connect"))
    )
    (net (code "67") (name "unconnected-(IC4-AUX_DA-Pad6)") (class "Default")
      (node (ref "IC4") (pin "6") (pinfunction "AUX_DA_6") (pintype "passive+no_connect"))
    )
    (net (code "68") (name "unconnected-(IC4-CLKIN-Pad1)") (class "Default")
      (node (ref "IC4") (pin "1") (pinfunction "CLKIN_1") (pintype "passive"))
    )
    (net (code "69") (name "unconnected-(IC4-NC_1-Pad2)") (class "Default")
      (node (ref "IC4") (pin "2") (pinfunction "NC_1_2") (pintype "passive+no_connect"))
    )
    (net (code "70") (name "unconnected-(IC4-NC_2-Pad3)") (class "Default")
      (node (ref "IC4") (pin "3") (pinfunction "NC_2_3") (pintype "passive+no_connect"))
    )
    (net (code "71") (name "unconnected-(IC4-NC_3-Pad4)") (class "Default")
      (node (ref "IC4") (pin "4") (pinfunction "NC_3_4") (pintype "passive+no_connect"))
    )
    (net (code "72") (name "unconnected-(IC4-NC_4-Pad5)") (class "Default")
      (node (ref "IC4") (pin "5") (pinfunction "NC_4_5") (pintype "passive+no_connect"))
    )
    (net (code "73") (name "unconnected-(IC4-NC_5-Pad14)") (class "Default")
      (node (ref "IC4") (pin "14") (pinfunction "NC_5_14") (pintype "passive+no_connect"))
    )
    (net (code "74") (name "unconnected-(IC4-NC_6-Pad15)") (class "Default")
      (node (ref "IC4") (pin "15") (pinfunction "NC_6_15") (pintype "passive+no_connect"))
    )
    (net (code "75") (name "unconnected-(IC4-NC_7-Pad16)") (class "Default")
      (node (ref "IC4") (pin "16") (pinfunction "NC_7_16") (pintype "passive+no_connect"))
    )
    (net (code "76") (name "unconnected-(IC4-NC_8-Pad17)") (class "Default")
      (node (ref "IC4") (pin "17") (pinfunction "NC_8_17") (pintype "passive+no_connect"))
    )
    (net (code "77") (name "unconnected-(IC4-RESV_1-Pad19)") (class "Default")
      (node (ref "IC4") (pin "19") (pinfunction "RESV_1_19") (pintype "passive"))
    )
    (net (code "78") (name "unconnected-(IC4-RESV_2-Pad21)") (class "Default")
      (node (ref "IC4") (pin "21") (pinfunction "RESV_2_21") (pintype "passive+no_connect"))
    )
    (net (code "79") (name "unconnected-(IC4-RESV_3-Pad22)") (class "Default")
      (node (ref "IC4") (pin "22") (pinfunction "RESV_3_22") (pintype "passive+no_connect"))
    )
    (net (code "80") (name "unconnected-(IC5-CTS-Pad23)") (class "Default")
      (node (ref "IC5") (pin "23") (pinfunction "CTS_23") (pintype "passive+no_connect"))
    )
    (net (code "81") (name "unconnected-(IC5-DCD-Pad1)") (class "Default")
      (node (ref "IC5") (pin "1") (pinfunction "DCD_1") (pintype "passive+no_connect"))
    )
    (net (code "82") (name "unconnected-(IC5-DSR-Pad27)") (class "Default")
      (node (ref "IC5") (pin "27") (pinfunction "DSR_27") (pintype "passive+no_connect"))
    )
    (net (code "83") (name "unconnected-(IC5-NC_1-Pad10)") (class "Default")
      (node (ref "IC5") (pin "10") (pinfunction "NC_1_10") (pintype "passive+no_connect"))
    )
    (net (code "84") (name "unconnected-(IC5-NC_2-Pad13)") (class "Default")
      (node (ref "IC5") (pin "13") (pinfunction "NC_2_13") (pintype "passive+no_connect"))
    )
    (net (code "85") (name "unconnected-(IC5-NC_3-Pad14)") (class "Default")
      (node (ref "IC5") (pin "14") (pinfunction "NC_3_14") (pintype "passive+no_connect"))
    )
    (net (code "86") (name "unconnected-(IC5-NC_4-Pad15)") (class "Default")
      (node (ref "IC5") (pin "15") (pinfunction "NC_4_15") (pintype "passive+no_connect"))
    )
    (net (code "87") (name "unconnected-(IC5-NC_5-Pad16)") (class "Default")
      (node (ref "IC5") (pin "16") (pinfunction "NC_5_16") (pintype "passive+no_connect"))
    )
    (net (code "88") (name "unconnected-(IC5-NC_6-Pad17)") (class "Default")
      (node (ref "IC5") (pin "17") (pinfunction "NC_6_17") (pintype "passive+no_connect"))
    )
    (net (code "89") (name "unconnected-(IC5-NC_7-Pad19)") (class "Default")
      (node (ref "IC5") (pin "19") (pinfunction "NC_7_19") (pintype "passive+no_connect"))
    )
    (net (code "90") (name "unconnected-(IC5-NC_8-Pad20)") (class "Default")
      (node (ref "IC5") (pin "20") (pinfunction "NC_8_20") (pintype "passive+no_connect"))
    )
    (net (code "91") (name "unconnected-(IC5-NC_9-Pad21)") (class "Default")
      (node (ref "IC5") (pin "21") (pinfunction "NC_9_21") (pintype "passive+no_connect"))
    )
    (net (code "92") (name "unconnected-(IC5-NC_10-Pad22)") (class "Default")
      (node (ref "IC5") (pin "22") (pinfunction "NC_10_22") (pintype "passive+no_connect"))
    )
    (net (code "93") (name "unconnected-(IC5-NC_{slash}_VPP-Pad18)") (class "Default")
      (node (ref "IC5") (pin "18") (pinfunction "NC_/_VPP_18") (pintype "passive+no_connect"))
    )
    (net (code "94") (name "unconnected-(IC5-RI-Pad2)") (class "Default")
      (node (ref "IC5") (pin "2") (pinfunction "RI_2") (pintype "passive+no_connect"))
    )
    (net (code "95") (name "unconnected-(IC5-SUSPEND-Pad12)") (class "Default")
      (node (ref "IC5") (pin "12") (pinfunction "SUSPEND_12") (pintype "passive+no_connect"))
    )
    (net (code "96") (name "unconnected-(IC5-~{RST}-Pad9)") (class "Default")
      (node (ref "IC5") (pin "9") (pinfunction "~{RST}_9") (pintype "passive+no_connect"))
    )
    (net (code "97") (name "unconnected-(IC5-~{SUSPEND}-Pad11)") (class "Default")
      (node (ref "IC5") (pin "11") (pinfunction "~{SUSPEND}_11") (pintype "passive+no_connect"))
    )
    (net (code "98") (name "unconnected-(J1-Pad4)") (class "Default")
      (node (ref "J1") (pin "4") (pinfunction "4_4") (pintype "passive+no_connect"))
    )
    (net (code "99") (name "unconnected-(U1-INT2-Pad1)") (class "Default")
      (node (ref "U1") (pin "1") (pinfunction "INT2_1") (pintype "bidirectional"))
    )
    (net (code "100") (name "unconnected-(U1-INT4-Pad13)") (class "Default")
      (node (ref "U1") (pin "13") (pinfunction "INT4_13") (pintype "bidirectional"))
    )
    (net (code "101") (name "unconnected-(U2-DRDY-Pad15)") (class "Default")
      (node (ref "U2") (pin "15") (pinfunction "DRDY_15") (pintype "bidirectional"))
    )
  )
)
